# ESP-C3-13-BREAKOUT.net
KiCad netlist of a schematic drawn in Altium Designer
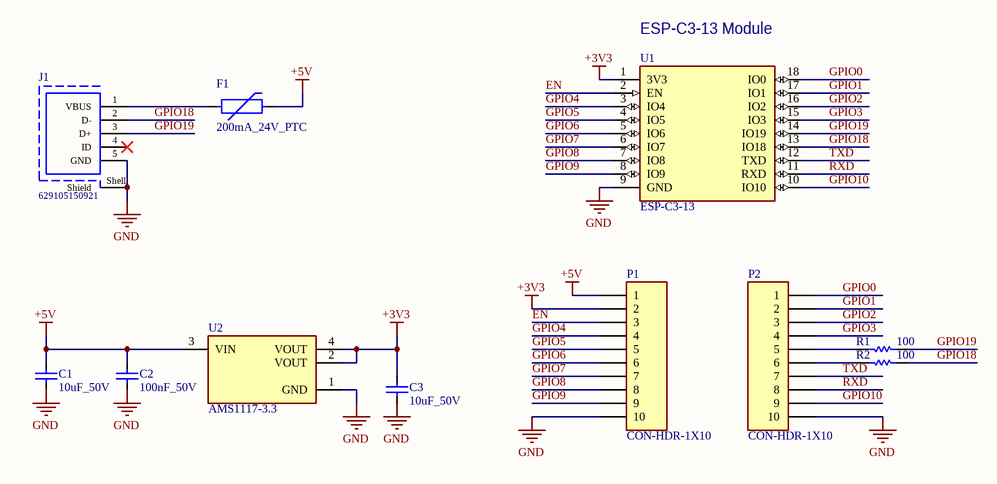
[diagram p0: ESP-C3-13-BREAKOUT.SchDoc]

(export (version "E")
  (design (tool "Eeschema 10.0.6"))
  (components
    (comp (ref "C1")
      (value "10uF_50V")
      (footprint "CustomLib-Package:C0805")
      (description "C0805 0.10 μF X7R 30ppm/°C 10.00% 50 V")
      (fields
        (field (name "MANUFACTURER") "KEMET")
        (field (name "MANUFACTURER PART NUMBER") "C0805C104K5RAC7411")
      )
      (libsource (lib "CustomLib-Package") (part "CAPACITOR"))
    )
    (comp (ref "C2")
      (value "100nF_50V")
      (footprint "CustomLib-Package:C0805")
      (description "C0805 0.10 μF X7R 30ppm/°C 10.00% 50 V")
      (fields
        (field (name "MANUFACTURER") "KEMET")
        (field (name "MANUFACTURER PART NUMBER") "C0805C104K5RAC7411")
      )
      (libsource (lib "CustomLib-Package") (part "CAPACITOR"))
    )
    (comp (ref "C3")
      (value "10uF_50V")
      (footprint "CustomLib-Package:C0805")
      (description "C0805 0.10 μF X7R 30ppm/°C 10.00% 50 V")
      (fields
        (field (name "MANUFACTURER") "KEMET")
        (field (name "MANUFACTURER PART NUMBER") "C0805C104K5RAC7411")
      )
      (libsource (lib "CustomLib-Package") (part "CAPACITOR"))
    )
    (comp (ref "F1")
      (value "200mA_24V_PTC")
      (footprint "CustomLib-Package:R1206")
      (description "FUSE PPTC 200MA (1206) 24V RESETTABLE")
      (fields (field (name "Comment") "NANOSMDC020F-2"))
      (libsource (lib "CustomLib-Package") (part "FUSE-PTC"))
    )
    (comp (ref "J1")
      (value "629105150921")
      (footprint "CON-MICRO-USB-B-SMD-WITH-HOLDER")
      (description "Micro USB 2.0 Type AB Receptacle WR-COM, Horizontal, SMT")
      (fields (field (name "MANUFACTURER") "Wurth Elektronik") (field (name "PUBLISHER") "WurthElektronik"))
      (libsource (lib "CustomLib-Package") (part "CON-MICRO-USB-AB-RCPT-SMD"))
    )
    (comp (ref "P1")
      (value "CON-HDR-1X10")
      (footprint "CON-HDR-1X10-2.54")
      (description "Pin Header, 10-Pin")
      (fields (field (name "PUBLISHER") "Altium Limited"))
      (libsource (lib "CustomLib-Package") (part "CON-HDR-1X10"))
    )
    (comp (ref "P2")
      (value "CON-HDR-1X10")
      (footprint "CON-HDR-1X10-2.54")
      (description "Pin Header, 10-Pin")
      (fields (field (name "PUBLISHER") "Altium Limited"))
      (libsource (lib "") (part "CON-HDR-1X10_1"))
    )
    (comp (ref "R1")
      (value "100")
      (footprint "R0805")
      (description "RES SMD 10K OHM 1% 1/8W 0805")
      (fields (field (name "TOLERANCE") "1%") (field (name "Comment") "CRG0805F10K"))
      (libsource (lib "CustomLib-Package") (part "RESISTOR"))
    )
    (comp (ref "R2")
      (value "100")
      (footprint "R0805")
      (description "RES SMD 10K OHM 1% 1/8W 0805")
      (fields (field (name "TOLERANCE") "1%") (field (name "Comment") "CRG0805F10K"))
      (libsource (lib "CustomLib-Package") (part "RESISTOR"))
    )
    (comp (ref "U1")
      (value "ESP-C3-13")
      (footprint "ESP-C3-13_NO-KEEPOUT")
      (fields (field (name "MP") "ESP32-C3-WROOM-02-N4") (field (name "MF") "Espressif Systems"))
      (libsource (lib "CustomLib-Package") (part "ESP-C3-13"))
    )
    (comp (ref "U2")
      (value "AMS1117-3.3")
      (footprint "CustomLib-Package:SOT-223")
      (description "IC REG LINEAR 3.3V 800MA SOT223")
      (libsource (lib "CustomLib-Package") (part "LD1117"))
    )
  )
  (nets
    (net (code "1") (name "+3V3") (class "Default")
      (node (ref "C3") (pin "1") (pinfunction "1_1") (pintype "passive"))
      (node (ref "P1") (pin "2") (pinfunction "2_2") (pintype "passive"))
      (node (ref "U1") (pin "1") (pinfunction "3V3_1") (pintype "power_in"))
      (node (ref "U2") (pin "2") (pinfunction "VOUT_2") (pintype "power_in"))
      (node (ref "U2") (pin "4") (pinfunction "VOUT_4") (pintype "power_in"))
    )
    (net (code "2") (name "+5V") (class "Default")
      (node (ref "C1") (pin "1") (pinfunction "1_1") (pintype "passive"))
      (node (ref "C2") (pin "1") (pinfunction "1_1") (pintype "passive"))
      (node (ref "F1") (pin "2") (pinfunction "2_2") (pintype "passive"))
      (node (ref "P1") (pin "1") (pinfunction "1_1") (pintype "passive"))
      (node (ref "U2") (pin "3") (pinfunction "VIN_3") (pintype "power_in"))
    )
    (net (code "3") (name "/EN") (class "Default")
      (node (ref "P1") (pin "3") (pinfunction "3_3") (pintype "passive"))
      (node (ref "U1") (pin "2") (pinfunction "EN_2") (pintype "input"))
    )
    (net (code "4") (name "/GPIO0") (class "Default")
      (node (ref "P2") (pin "1") (pinfunction "1_1") (pintype "passive"))
      (node (ref "U1") (pin "18") (pinfunction "IO0_18") (pintype "bidirectional"))
    )
    (net (code "5") (name "/GPIO1") (class "Default")
      (node (ref "P2") (pin "2") (pinfunction "2_2") (pintype "passive"))
      (node (ref "U1") (pin "17") (pinfunction "IO1_17") (pintype "bidirectional"))
    )
    (net (code "6") (name "/GPIO2") (class "Default")
      (node (ref "P2") (pin "3") (pinfunction "3_3") (pintype "passive"))
      (node (ref "U1") (pin "16") (pinfunction "IO2_16") (pintype "bidirectional"))
    )
    (net (code "7") (name "/GPIO3") (class "Default")
      (node (ref "P2") (pin "4") (pinfunction "4_4") (pintype "passive"))
      (node (ref "U1") (pin "15") (pinfunction "IO3_15") (pintype "bidirectional"))
    )
    (net (code "8") (name "/GPIO4") (class "Default")
      (node (ref "P1") (pin "4") (pinfunction "4_4") (pintype "passive"))
      (node (ref "U1") (pin "3") (pinfunction "IO4_3") (pintype "bidirectional"))
    )
    (net (code "9") (name "/GPIO5") (class "Default")
      (node (ref "P1") (pin "5") (pinfunction "5_5") (pintype "passive"))
      (node (ref "U1") (pin "4") (pinfunction "IO5_4") (pintype "bidirectional"))
    )
    (net (code "10") (name "/GPIO6") (class "Default")
      (node (ref "P1") (pin "6") (pinfunction "6_6") (pintype "passive"))
      (node (ref "U1") (pin "5") (pinfunction "IO6_5") (pintype "bidirectional"))
    )
    (net (code "11") (name "/GPIO7") (class "Default")
      (node (ref "P1") (pin "7") (pinfunction "7_7") (pintype "passive"))
      (node (ref "U1") (pin "6") (pinfunction "IO7_6") (pintype "bidirectional"))
    )
    (net (code "12") (name "/GPIO8") (class "Default")
      (node (ref "P1") (pin "8") (pinfunction "8_8") (pintype "passive"))
      (node (ref "U1") (pin "7") (pinfunction "IO8_7") (pintype "bidirectional"))
    )
    (net (code "13") (name "/GPIO9") (class "Default")
      (node (ref "P1") (pin "9") (pinfunction "9_9") (pintype "passive"))
      (node (ref "U1") (pin "8") (pinfunction "IO9_8") (pintype "bidirectional"))
    )
    (net (code "14") (name "/GPIO10") (class "Default")
      (node (ref "P2") (pin "9") (pinfunction "9_9") (pintype "passive"))
      (node (ref "U1") (pin "10") (pinfunction "IO10_10") (pintype "bidirectional"))
    )
    (net (code "15") (name "/GPIO18") (class "Default")
      (node (ref "J1") (pin "2") (pinfunction "D-_2") (pintype "passive"))
      (node (ref "R2") (pin "1") (pinfunction "1_1") (pintype "passive"))
      (node (ref "U1") (pin "13") (pinfunction "IO18_13") (pintype "bidirectional"))
    )
    (net (code "16") (name "/GPIO19") (class "Default")
      (node (ref "J1") (pin "3") (pinfunction "D+_3") (pintype "passive"))
      (node (ref "R1") (pin "1") (pinfunction "1_1") (pintype "passive"))
      (node (ref "U1") (pin "14") (pinfunction "IO19_14") (pintype "bidirectional"))
    )
    (net (code "17") (name "/RXD") (class "Default")
      (node (ref "P2") (pin "8") (pinfunction "8_8") (pintype "passive"))
      (node (ref "U1") (pin "11") (pinfunction "RXD_11") (pintype "bidirectional"))
    )
    (net (code "18") (name "/TXD") (class "Default")
      (node (ref "P2") (pin "7") (pinfunction "7_7") (pintype "passive"))
      (node (ref "U1") (pin "12") (pinfunction "TXD_12") (pintype "bidirectional"))
    )
    (net (code "19") (name "GND") (class "Default")
      (node (ref "C1") (pin "2") (pinfunction "2_2") (pintype "passive"))
      (node (ref "C2") (pin "2") (pinfunction "2_2") (pintype "passive"))
      (node (ref "C3") (pin "2") (pinfunction "2_2") (pintype "passive"))
      (node (ref "J1") (pin "5") (pinfunction "GND_5") (pintype "passive"))
      (node (ref "J1") (pin "Shell") (pinfunction "Shield_Shell") (pintype "passive"))
      (node (ref "P1") (pin "10") (pinfunction "10_10") (pintype "passive"))
      (node (ref "P2") (pin "10") (pinfunction "10_10") (pintype "passive"))
      (node (ref "U1") (pin "9") (pinfunction "GND_9") (pintype "power_in"))
      (node (ref "U2") (pin "1") (pinfunction "GND_1") (pintype "power_in"))
    )
    (net (code "20") (name "Net-(J1-VBUS)") (class "Default")
      (node (ref "F1") (pin "1") (pinfunction "1_1") (pintype "passive"))
      (node (ref "J1") (pin "1") (pinfunction "VBUS_1") (pintype "passive"))
    )
    (net (code "21") (name "Net-(P2-Pad5)") (class "Default")
      (node (ref "P2") (pin "5") (pinfunction "5_5") (pintype "passive"))
      (node (ref "R1") (pin "2") (pinfunction "2_2") (pintype "passive"))
    )
    (net (code "22") (name "Net-(P2-Pad6)") (class "Default")
      (node (ref "P2") (pin "6") (pinfunction "6_6") (pintype "passive"))
      (node (ref "R2") (pin "2") (pinfunction "2_2") (pintype "passive"))
    )
    (net (code "23") (name "unconnected-(J1-ID-Pad4)") (class "Default")
      (node (ref "J1") (pin "4") (pinfunction "ID_4") (pintype "passive+no_connect"))
    )
  )
)
